# main.net
KiCad netlist of a schematic drawn in Altium Designer
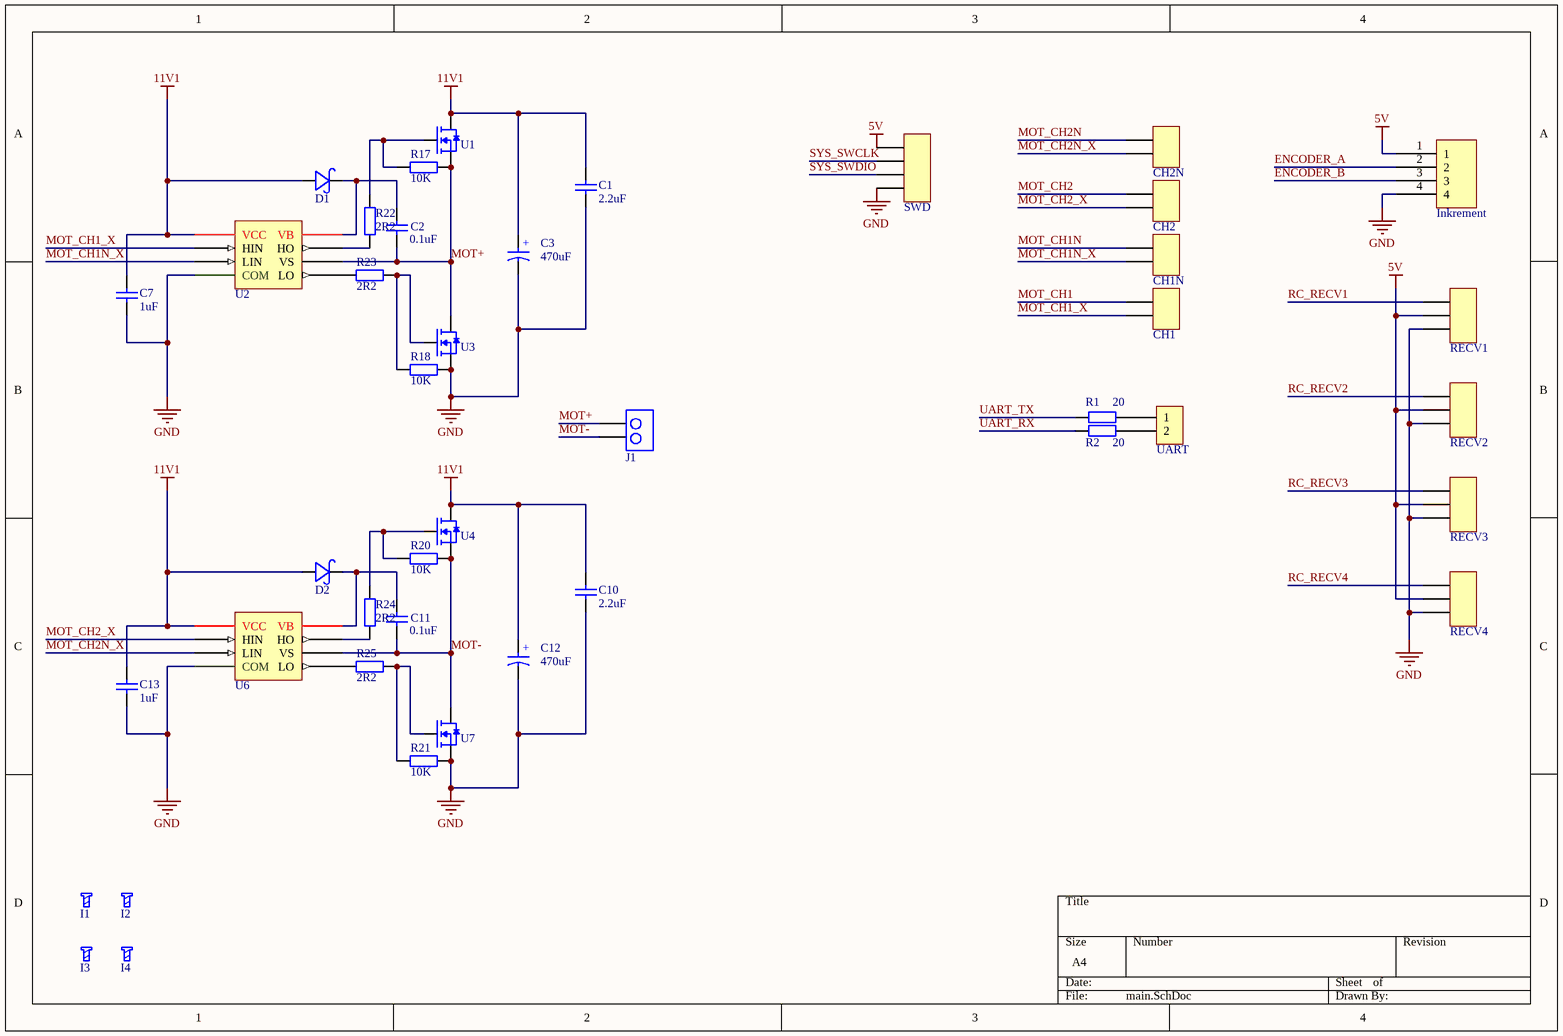
[diagram p0: main.SchDoc]

(export (version "E")
  (design (tool "Eeschema 10.0.6"))
  (components
    (comp (ref "C1")
      (value "R60DF4220506AJ")
      (footprint "10mm lead spacing CAP")
      (description "General Purpose Metallized Polyester Film Capacitor, 2.2 uF, 40 VAC, 63 VDC , 5 %")
      (fields (field (name "CAPACITANCE") "2.2uF"))
      (libsource (lib "HomeProjects") (part "R60DF4220506AJ"))
    )
    (comp (ref "C2")
      (value "VJ0805Y104JXATW1BC")
      (footprint "0805")
      (description "SMD Multilayer Ceramic Capacitor, 0805 [2012 Metric], 0.1 µF, 50 V, ± 5%, X7R, VJ Series")
      (fields (field (name "CAPACITANCE") "0.1uF"))
      (libsource (lib "RobonAUT") (part "VJ0805Y104JXATW1BC"))
    )
    (comp (ref "C3")
      (value "EEU-FR1V471")
      (footprint "5mm lead spacing ELCAP")
      (description "Aluminum Electrolytic Capacitors, 470uF, Low ESR")
      (fields (field (name "CAPACITANCE") "470uF"))
      (libsource (lib "HomeProjects") (part "EEU-FR1V471"))
    )
    (comp (ref "C7")
      (value "VJ0805Y105KXQTW1BC")
      (footprint "0805")
      (description "SMD Multilayer Ceramic Capacitor, 0805 [2012 Metric], 1 µF, 10 V, ± 10%, X7R, VJ Series")
      (fields (field (name "CAPACITANCE") "1uF"))
      (libsource (lib "RobonAUT") (part "VJ0805Y105KXQTW1BC"))
    )
    (comp (ref "C10")
      (value "R60DF4220506AJ")
      (footprint "10mm lead spacing CAP")
      (description "General Purpose Metallized Polyester Film Capacitor, 2.2 uF, 40 VAC, 63 VDC , 5 %")
      (fields (field (name "CAPACITANCE") "2.2uF"))
      (libsource (lib "HomeProjects") (part "R60DF4220506AJ"))
    )
    (comp (ref "C11")
      (value "VJ0805Y104JXATW1BC")
      (footprint "0805")
      (description "SMD Multilayer Ceramic Capacitor, 0805 [2012 Metric], 0.1 µF, 50 V, ± 5%, X7R, VJ Series")
      (fields (field (name "CAPACITANCE") "0.1uF"))
      (libsource (lib "RobonAUT") (part "VJ0805Y104JXATW1BC"))
    )
    (comp (ref "C12")
      (value "EEU-FR1V471")
      (footprint "5mm lead spacing ELCAP")
      (description "Aluminum Electrolytic Capacitors, 470uF, Low ESR")
      (fields (field (name "CAPACITANCE") "470uF"))
      (libsource (lib "HomeProjects") (part "EEU-FR1V471"))
    )
    (comp (ref "C13")
      (value "VJ0805Y105KXQTW1BC")
      (footprint "0805")
      (description "SMD Multilayer Ceramic Capacitor, 0805 [2012 Metric], 1 µF, 10 V, ± 10%, X7R, VJ Series")
      (fields (field (name "CAPACITANCE") "1uF"))
      (libsource (lib "RobonAUT") (part "VJ0805Y105KXQTW1BC"))
    )
    (comp (ref "CH1")
      (value "2-Pin Header")
      (footprint "2-Pin Header")
      (description "TÜSKESOR 2 P SMD SPHSS220-B02-4/3 (T-T) 2mm PIN 0.5x0.5 TÖRDELHETÖ [ 43-10-37 ]")
      (libsource (lib "RobonAUT") (part "2-Pin Header"))
    )
    (comp (ref "CH1N")
      (value "2-Pin Header")
      (footprint "2-Pin Header")
      (description "TÜSKESOR 2 P SMD SPHSS220-B02-4/3 (T-T) 2mm PIN 0.5x0.5 TÖRDELHETÖ [ 43-10-37 ]")
      (libsource (lib "RobonAUT") (part "2-Pin Header"))
    )
    (comp (ref "CH2")
      (value "2-Pin Header")
      (footprint "2-Pin Header")
      (description "TÜSKESOR 2 P SMD SPHSS220-B02-4/3 (T-T) 2mm PIN 0.5x0.5 TÖRDELHETÖ [ 43-10-37 ]")
      (libsource (lib "RobonAUT") (part "2-Pin Header"))
    )
    (comp (ref "CH2N")
      (value "2-Pin Header")
      (footprint "2-Pin Header")
      (description "TÜSKESOR 2 P SMD SPHSS220-B02-4/3 (T-T) 2mm PIN 0.5x0.5 TÖRDELHETÖ [ 43-10-37 ]")
      (libsource (lib "RobonAUT") (part "2-Pin Header"))
    )
    (comp (ref "D1")
      (value "SS32A")
      (footprint "Home:DO-214AC(SMA)")
      (description "3A 40V DO-214AC SCH.RECT. SS34A (YET) SMA (SK34A;SX34) [ 83-02-56 ]")
      (libsource (lib "RobonAUT") (part "SS32A"))
    )
    (comp (ref "D2")
      (value "SS32A")
      (footprint "Home:DO-214AC(SMA)")
      (description "3A 40V DO-214AC SCH.RECT. SS34A (YET) SMA (SK34A;SX34) [ 83-02-56 ]")
      (libsource (lib "RobonAUT") (part "SS32A"))
    )
    (comp (ref "I1")
      (value "M3 screw drillhole")
      (footprint "3mm diameter drill")
      (description "5mm diameter via with 3mm hole")
      (libsource (lib "HomeProjects") (part "M3 screw drillhole"))
    )
    (comp (ref "I2")
      (value "M3 screw drillhole")
      (footprint "3mm diameter drill")
      (description "5mm diameter via with 3mm hole")
      (libsource (lib "HomeProjects") (part "M3 screw drillhole"))
    )
    (comp (ref "I3")
      (value "M3 screw drillhole")
      (footprint "3mm diameter drill")
      (description "5mm diameter via with 3mm hole")
      (libsource (lib "HomeProjects") (part "M3 screw drillhole"))
    )
    (comp (ref "I4")
      (value "M3 screw drillhole")
      (footprint "3mm diameter drill")
      (description "5mm diameter via with 3mm hole")
      (libsource (lib "HomeProjects") (part "M3 screw drillhole"))
    )
    (comp (ref "Inkrement")
      (value "43-17-42")
      (footprint "43-17-42")
      (description "TÁPCSATL. 2.00mm 4P APA 90° NCW200S-04R (G-S) FORR. [ 43-17-42 ]")
      (libsource (lib "RobonAUT") (part "43-17-42"))
    )
    (comp (ref "J1")
      (value "1935776")
      (footprint "PT 2,5/ 2-5,0-H")
      (libsource (lib "HomeProjects") (part "1935776"))
    )
    (comp (ref "R1")
      (value "CR0805-FX-20R0ELF")
      (footprint "0805")
      (description "Thick Film Resistors - SMD 20ohm 1%")
      (fields (field (name "RESISTANCE") "20"))
      (libsource (lib "HomeProjects") (part "CR0805-FX-20R0ELF"))
    )
    (comp (ref "R2")
      (value "CR0805-FX-20R0ELF")
      (footprint "0805")
      (description "Thick Film Resistors - SMD 20ohm 1%")
      (fields (field (name "RESISTANCE") "20"))
      (libsource (lib "HomeProjects") (part "CR0805-FX-20R0ELF"))
    )
    (comp (ref "R17")
      (value "10K")
      (footprint "FP_0805_RES")
      (description "Resistor")
      (fields (field (name "TOLERANCE") "5%") (field (name "POWER") "125mW"))
      (libsource (lib "hallglib") (part "RES 10K"))
    )
    (comp (ref "R18")
      (value "10K")
      (footprint "FP_0805_RES")
      (description "Resistor")
      (fields (field (name "TOLERANCE") "5%") (field (name "POWER") "125mW"))
      (libsource (lib "hallglib") (part "RES 10K"))
    )
    (comp (ref "R20")
      (value "10K")
      (footprint "FP_0805_RES")
      (description "Resistor")
      (fields (field (name "TOLERANCE") "5%") (field (name "POWER") "125mW"))
      (libsource (lib "hallglib") (part "RES 10K"))
    )
    (comp (ref "R21")
      (value "10K")
      (footprint "FP_0805_RES")
      (description "Resistor")
      (fields (field (name "TOLERANCE") "5%") (field (name "POWER") "125mW"))
      (libsource (lib "hallglib") (part "RES 10K"))
    )
    (comp (ref "R22")
      (value "2R2")
      (footprint "FP_0805_RES")
      (description "Resistor")
      (fields (field (name "TOLERANCE") "5%") (field (name "POWER") "125mW"))
      (libsource (lib "") (part "RES 2R2_1"))
    )
    (comp (ref "R23")
      (value "2R2")
      (footprint "FP_0805_RES")
      (description "Resistor")
      (fields (field (name "TOLERANCE") "5%") (field (name "POWER") "125mW"))
      (libsource (lib "hallglib") (part "RES 2R2"))
    )
    (comp (ref "R24")
      (value "2R2")
      (footprint "FP_0805_RES")
      (description "Resistor")
      (fields (field (name "TOLERANCE") "5%") (field (name "POWER") "125mW"))
      (libsource (lib "") (part "RES 2R2_1"))
    )
    (comp (ref "R25")
      (value "2R2")
      (footprint "FP_0805_RES")
      (description "Resistor")
      (fields (field (name "TOLERANCE") "5%") (field (name "POWER") "125mW"))
      (libsource (lib "hallglib") (part "RES 2R2"))
    )
    (comp (ref "RECV1")
      (value "3-Pin HEADER")
      (footprint "3-Pin HEADER")
      (libsource (lib "RobonAUT") (part "3-Pin HEADER"))
    )
    (comp (ref "RECV2")
      (value "3-Pin HEADER")
      (footprint "3-Pin HEADER")
      (libsource (lib "RobonAUT") (part "3-Pin HEADER"))
    )
    (comp (ref "RECV3")
      (value "3-Pin HEADER")
      (footprint "3-Pin HEADER")
      (libsource (lib "RobonAUT") (part "3-Pin HEADER"))
    )
    (comp (ref "RECV4")
      (value "3-Pin HEADER")
      (footprint "3-Pin HEADER")
      (libsource (lib "RobonAUT") (part "3-Pin HEADER"))
    )
    (comp (ref "SWD")
      (value "4-Pin Header")
      (footprint "4-Pin Header")
      (libsource (lib "RobonAUT") (part "4-Pin Header"))
    )
    (comp (ref "U1")
      (value "IRLR8743TRLPBF")
      (footprint "TO-252 (DPAK)")
      (description "HEXFET2Power MOSFET, Vdss=30V, Rdson=3.1mOhm, Qg=39nC, Id=160A")
      (libsource (lib "HomeProjects") (part "IRLR8743TRLPBF"))
    )
    (comp (ref "U2")
      (value "IRS2186STRPBF")
      (footprint "8-Pin SOIC")
      (description "High and Low Side Driver")
      (libsource (lib "HomeProjects") (part "IRS2186STRPBF"))
    )
    (comp (ref "U3")
      (value "IRLR8743TRLPBF")
      (footprint "TO-252 (DPAK)")
      (description "HEXFET2Power MOSFET, Vdss=30V, Rdson=3.1mOhm, Qg=39nC, Id=160A")
      (libsource (lib "HomeProjects") (part "IRLR8743TRLPBF"))
    )
    (comp (ref "U4")
      (value "IRLR8743TRLPBF")
      (footprint "TO-252 (DPAK)")
      (description "HEXFET2Power MOSFET, Vdss=30V, Rdson=3.1mOhm, Qg=39nC, Id=160A")
      (libsource (lib "HomeProjects") (part "IRLR8743TRLPBF"))
    )
    (comp (ref "U6")
      (value "IRS2186STRPBF")
      (footprint "8-Pin SOIC")
      (description "High and Low Side Driver")
      (libsource (lib "HomeProjects") (part "IRS2186STRPBF"))
    )
    (comp (ref "U7")
      (value "IRLR8743TRLPBF")
      (footprint "TO-252 (DPAK)")
      (description "HEXFET2Power MOSFET, Vdss=30V, Rdson=3.1mOhm, Qg=39nC, Id=160A")
      (libsource (lib "HomeProjects") (part "IRLR8743TRLPBF"))
    )
    (comp (ref "UART")
      (value "2-Pin HEADER")
      (footprint "2-Pin Header")
      (libsource (lib "HomeProjects") (part "2-Pin HEADER"))
    )
  )
  (nets
    (net (code "1") (name "/ENCODER_A") (class "Default")
      (node (ref "Inkrement") (pin "2") (pinfunction "2_2") (pintype "passive"))
    )
    (net (code "2") (name "/ENCODER_B") (class "Default")
      (node (ref "Inkrement") (pin "3") (pinfunction "3_3") (pintype "passive"))
    )
    (net (code "3") (name "/MOT+") (class "Default")
      (node (ref "C2") (pin "1") (pinfunction "1_1") (pintype "passive"))
      (node (ref "J1") (pin "1") (pinfunction "1_1") (pintype "passive"))
      (node (ref "R17") (pin "2") (pinfunction "2_2") (pintype "passive"))
      (node (ref "U1") (pin "S") (pinfunction "S_S") (pintype "passive"))
      (node (ref "U2") (pin "6") (pinfunction "VS_6") (pintype "passive"))
      (node (ref "U3") (pin "D") (pinfunction "D_D") (pintype "passive"))
    )
    (net (code "4") (name "/MOT-") (class "Default")
      (node (ref "C11") (pin "1") (pinfunction "1_1") (pintype "passive"))
      (node (ref "J1") (pin "2") (pinfunction "2_2") (pintype "passive"))
      (node (ref "R20") (pin "2") (pinfunction "2_2") (pintype "passive"))
      (node (ref "U4") (pin "S") (pinfunction "S_S") (pintype "passive"))
      (node (ref "U6") (pin "6") (pinfunction "VS_6") (pintype "passive"))
      (node (ref "U7") (pin "D") (pinfunction "D_D") (pintype "passive"))
    )
    (net (code "5") (name "/MOT_CH1") (class "Default")
      (node (ref "CH1") (pin "1") (pinfunction "1_1") (pintype "passive"))
    )
    (net (code "6") (name "/MOT_CH1N") (class "Default")
      (node (ref "CH1N") (pin "1") (pinfunction "1_1") (pintype "passive"))
    )
    (net (code "7") (name "/MOT_CH1N_X") (class "Default")
      (node (ref "CH1N") (pin "2") (pinfunction "2_2") (pintype "passive"))
      (node (ref "U2") (pin "2") (pinfunction "LIN_2") (pintype "input"))
    )
    (net (code "8") (name "/MOT_CH1_X") (class "Default")
      (node (ref "CH1") (pin "2") (pinfunction "2_2") (pintype "passive"))
      (node (ref "U2") (pin "1") (pinfunction "HIN_1") (pintype "input"))
    )
    (net (code "9") (name "/MOT_CH2") (class "Default")
      (node (ref "CH2") (pin "1") (pinfunction "1_1") (pintype "passive"))
    )
    (net (code "10") (name "/MOT_CH2N") (class "Default")
      (node (ref "CH2N") (pin "1") (pinfunction "1_1") (pintype "passive"))
    )
    (net (code "11") (name "/MOT_CH2N_X") (class "Default")
      (node (ref "CH2N") (pin "2") (pinfunction "2_2") (pintype "passive"))
      (node (ref "U6") (pin "2") (pinfunction "LIN_2") (pintype "input"))
    )
    (net (code "12") (name "/MOT_CH2_X") (class "Default")
      (node (ref "CH2") (pin "2") (pinfunction "2_2") (pintype "passive"))
      (node (ref "U6") (pin "1") (pinfunction "HIN_1") (pintype "input"))
    )
    (net (code "13") (name "/RC_RECV1") (class "Default")
      (node (ref "RECV1") (pin "1") (pinfunction "1_1") (pintype "passive"))
    )
    (net (code "14") (name "/RC_RECV2") (class "Default")
      (node (ref "RECV2") (pin "1") (pinfunction "1_1") (pintype "passive"))
    )
    (net (code "15") (name "/RC_RECV3") (class "Default")
      (node (ref "RECV3") (pin "1") (pinfunction "1_1") (pintype "passive"))
    )
    (net (code "16") (name "/RC_RECV4") (class "Default")
      (node (ref "RECV4") (pin "1") (pinfunction "1_1") (pintype "passive"))
    )
    (net (code "17") (name "/SYS_SWCLK") (class "Default")
      (node (ref "SWD") (pin "2") (pinfunction "2_2") (pintype "passive"))
    )
    (net (code "18") (name "/SYS_SWDIO") (class "Default")
      (node (ref "SWD") (pin "3") (pinfunction "3_3") (pintype "passive"))
    )
    (net (code "19") (name "/UART_RX") (class "Default")
      (node (ref "R2") (pin "1") (pinfunction "1_1") (pintype "passive"))
    )
    (net (code "20") (name "/UART_TX") (class "Default")
      (node (ref "R1") (pin "1") (pinfunction "1_1") (pintype "passive"))
    )
    (net (code "21") (name "5V") (class "Default")
      (node (ref "Inkrement") (pin "1") (pinfunction "1_1") (pintype "passive"))
      (node (ref "RECV1") (pin "2") (pinfunction "2_2") (pintype "passive"))
      (node (ref "RECV2") (pin "2") (pinfunction "2_2") (pintype "passive"))
      (node (ref "RECV3") (pin "2") (pinfunction "2_2") (pintype "passive"))
      (node (ref "RECV4") (pin "2") (pinfunction "2_2") (pintype "passive"))
      (node (ref "SWD") (pin "1") (pinfunction "1_1") (pintype "passive"))
    )
    (net (code "22") (name "11V1") (class "Default")
      (node (ref "C1") (pin "2") (pinfunction "2_2") (pintype "passive"))
      (node (ref "C10") (pin "2") (pinfunction "2_2") (pintype "passive"))
      (node (ref "C12") (pin "1") (pinfunction "1_1") (pintype "passive"))
      (node (ref "C13") (pin "2") (pinfunction "2_2") (pintype "passive"))
      (node (ref "C3") (pin "1") (pinfunction "1_1") (pintype "passive"))
      (node (ref "C7") (pin "2") (pinfunction "2_2") (pintype "passive"))
      (node (ref "D1") (pin "A") (pinfunction "A_A") (pintype "passive"))
      (node (ref "D2") (pin "A") (pinfunction "A_A") (pintype "passive"))
      (node (ref "U1") (pin "D") (pinfunction "D_D") (pintype "passive"))
      (node (ref "U2") (pin "5") (pinfunction "VCC_5") (pintype "power_in"))
      (node (ref "U4") (pin "D") (pinfunction "D_D") (pintype "passive"))
      (node (ref "U6") (pin "5") (pinfunction "VCC_5") (pintype "power_in"))
    )
    (net (code "23") (name "GND") (class "Default")
      (node (ref "C1") (pin "1") (pinfunction "1_1") (pintype "passive"))
      (node (ref "C10") (pin "1") (pinfunction "1_1") (pintype "passive"))
      (node (ref "C12") (pin "2") (pinfunction "2_2") (pintype "passive"))
      (node (ref "C13") (pin "1") (pinfunction "1_1") (pintype "passive"))
      (node (ref "C3") (pin "2") (pinfunction "2_2") (pintype "passive"))
      (node (ref "C7") (pin "1") (pinfunction "1_1") (pintype "passive"))
      (node (ref "Inkrement") (pin "4") (pinfunction "4_4") (pintype "passive"))
      (node (ref "R18") (pin "2") (pinfunction "2_2") (pintype "passive"))
      (node (ref "R21") (pin "2") (pinfunction "2_2") (pintype "passive"))
      (node (ref "RECV1") (pin "3") (pinfunction "3_3") (pintype "passive"))
      (node (ref "RECV2") (pin "3") (pinfunction "3_3") (pintype "passive"))
      (node (ref "RECV3") (pin "3") (pinfunction "3_3") (pintype "passive"))
      (node (ref "RECV4") (pin "3") (pinfunction "3_3") (pintype "passive"))
      (node (ref "SWD") (pin "4") (pinfunction "4_4") (pintype "passive"))
      (node (ref "U2") (pin "3") (pinfunction "COM_3") (pintype "power_in"))
      (node (ref "U3") (pin "S") (pinfunction "S_S") (pintype "passive"))
      (node (ref "U6") (pin "3") (pinfunction "COM_3") (pintype "power_in"))
      (node (ref "U7") (pin "S") (pinfunction "S_S") (pintype "passive"))
    )
    (net (code "24") (name "Net-(R1-Pad2)") (class "Default")
      (node (ref "R1") (pin "2") (pinfunction "2_2") (pintype "passive"))
      (node (ref "UART") (pin "1") (pinfunction "1_1") (pintype "passive"))
    )
    (net (code "25") (name "Net-(R2-Pad2)") (class "Default")
      (node (ref "R2") (pin "2") (pinfunction "2_2") (pintype "passive"))
      (node (ref "UART") (pin "2") (pinfunction "2_2") (pintype "passive"))
    )
    (net (code "26") (name "Net-(R17-Pad1)") (class "Default")
      (node (ref "R17") (pin "1") (pinfunction "1_1") (pintype "passive"))
      (node (ref "R22") (pin "2") (pinfunction "2_2") (pintype "passive"))
      (node (ref "U1") (pin "G") (pinfunction "G_G") (pintype "passive"))
    )
    (net (code "27") (name "Net-(R18-Pad1)") (class "Default")
      (node (ref "R18") (pin "1") (pinfunction "1_1") (pintype "passive"))
      (node (ref "R23") (pin "1") (pinfunction "1_1") (pintype "passive"))
      (node (ref "U3") (pin "G") (pinfunction "G_G") (pintype "passive"))
    )
    (net (code "28") (name "Net-(R20-Pad1)") (class "Default")
      (node (ref "R20") (pin "1") (pinfunction "1_1") (pintype "passive"))
      (node (ref "R24") (pin "2") (pinfunction "2_2") (pintype "passive"))
      (node (ref "U4") (pin "G") (pinfunction "G_G") (pintype "passive"))
    )
    (net (code "29") (name "Net-(R21-Pad1)") (class "Default")
      (node (ref "R21") (pin "1") (pinfunction "1_1") (pintype "passive"))
      (node (ref "R25") (pin "1") (pinfunction "1_1") (pintype "passive"))
      (node (ref "U7") (pin "G") (pinfunction "G_G") (pintype "passive"))
    )
    (net (code "30") (name "Net-(U2-HO)") (class "Default")
      (node (ref "R22") (pin "1") (pinfunction "1_1") (pintype "passive"))
      (node (ref "U2") (pin "7") (pinfunction "HO_7") (pintype "output"))
    )
    (net (code "31") (name "Net-(U2-LO)") (class "Default")
      (node (ref "R23") (pin "2") (pinfunction "2_2") (pintype "passive"))
      (node (ref "U2") (pin "4") (pinfunction "LO_4") (pintype "output"))
    )
    (net (code "32") (name "Net-(U2-VB)") (class "Default")
      (node (ref "C2") (pin "2") (pinfunction "2_2") (pintype "passive"))
      (node (ref "D1") (pin "K") (pinfunction "K_K") (pintype "passive"))
      (node (ref "U2") (pin "8") (pinfunction "VB_8") (pintype "power_in"))
    )
    (net (code "33") (name "Net-(U6-HO)") (class "Default")
      (node (ref "R24") (pin "1") (pinfunction "1_1") (pintype "passive"))
      (node (ref "U6") (pin "7") (pinfunction "HO_7") (pintype "output"))
    )
    (net (code "34") (name "Net-(U6-LO)") (class "Default")
      (node (ref "R25") (pin "2") (pinfunction "2_2") (pintype "passive"))
      (node (ref "U6") (pin "4") (pinfunction "LO_4") (pintype "output"))
    )
    (net (code "35") (name "Net-(U6-VB)") (class "Default")
      (node (ref "C11") (pin "2") (pinfunction "2_2") (pintype "passive"))
      (node (ref "D2") (pin "K") (pinfunction "K_K") (pintype "passive"))
      (node (ref "U6") (pin "8") (pinfunction "VB_8") (pintype "power_in"))
    )
  )
)
